# LSM6DSOTR.net
KiCad netlist of a schematic drawn in Altium Designer
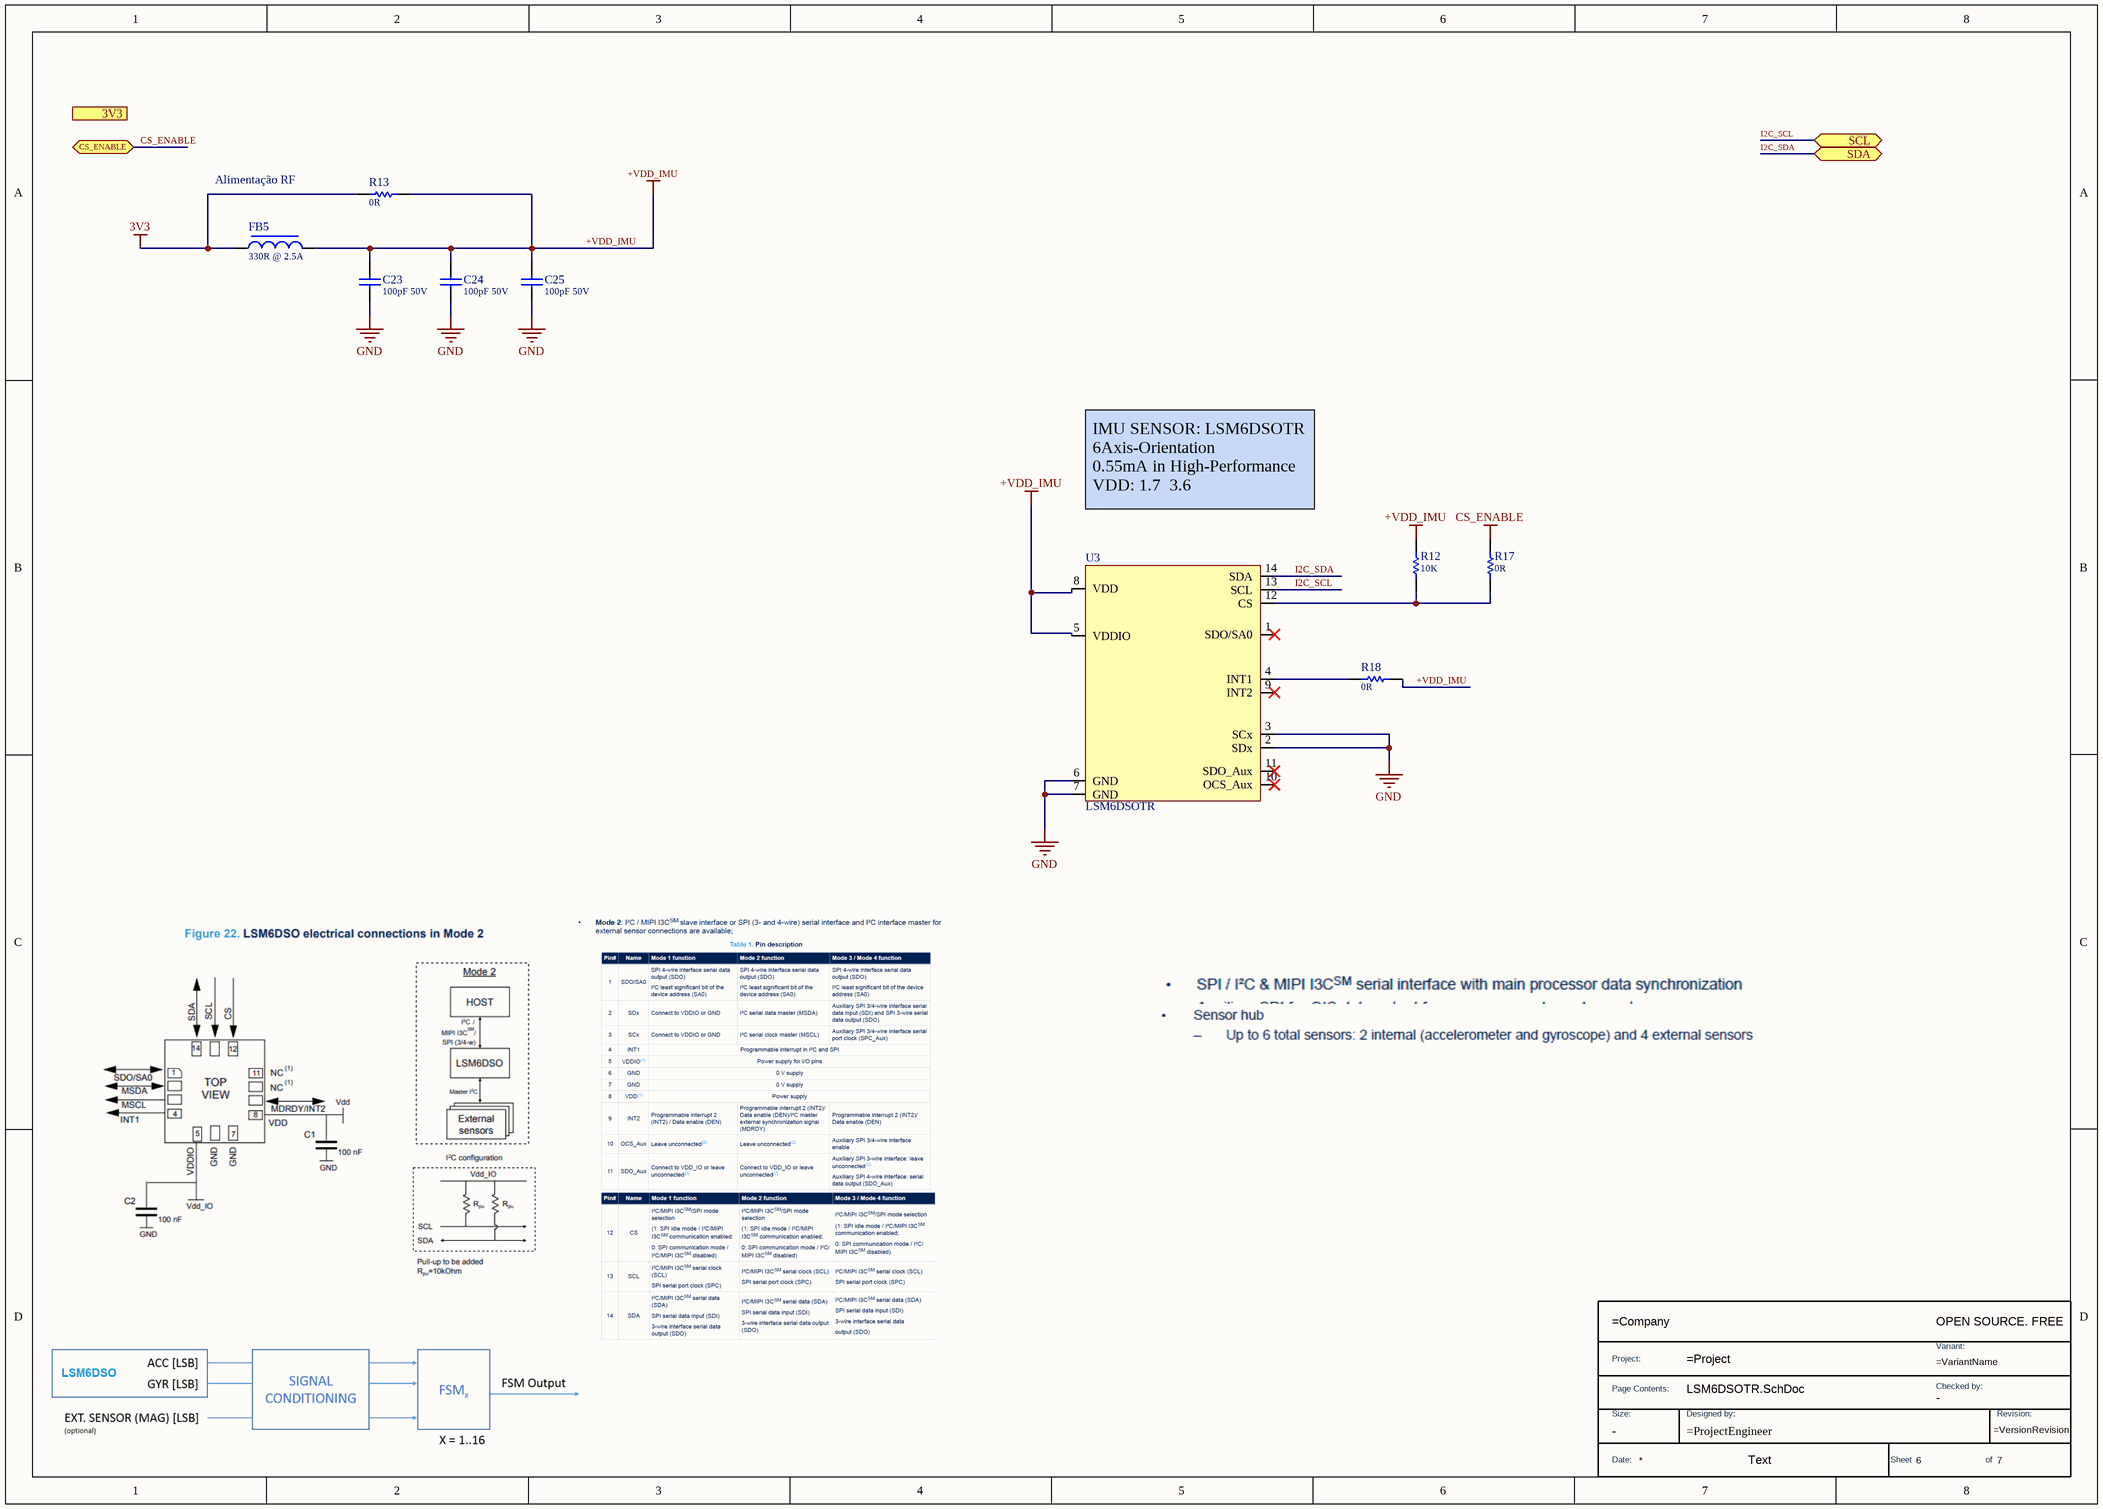
[diagram p0: LSM6DSOTR.SchDoc]

(export (version "E")
  (design (tool "Eeschema 10.0.6"))
  (components
    (comp (ref "C23")
      (value "CC0805JRNPO9BN101")
      (footprint "CAP_0805")
      (description "CAP CER 100PF 50V C0G/NPO 0805")
      (fields (field (name "MANUFACTURER") "YAGEO") (field (name "VALOR") "100pF 50V"))
      (libsource (lib "OBDH_Ed02") (part "CC0805JRNPO9BN101"))
    )
    (comp (ref "C24")
      (value "CC0805JRNPO9BN101")
      (footprint "CAP_0805")
      (description "CAP CER 100PF 50V C0G/NPO 0805")
      (fields (field (name "MANUFACTURER") "YAGEO") (field (name "VALOR") "100pF 50V"))
      (libsource (lib "OBDH_Ed02") (part "CC0805JRNPO9BN101"))
    )
    (comp (ref "C25")
      (value "CC0805JRNPO9BN101")
      (footprint "CAP_0805")
      (description "CAP CER 100PF 50V C0G/NPO 0805")
      (fields (field (name "MANUFACTURER") "YAGEO") (field (name "VALOR") "100pF 50V"))
      (libsource (lib "OBDH_Ed02") (part "CC0805JRNPO9BN101"))
    )
    (comp (ref "FB5")
      (value "MPZ2012S331AT000")
      (footprint "IND_0805")
      (description "FERRITE BEAD 330 OHM 0805 1LN")
      (fields (field (name "MANUFACTURER") "TDK Corporation") (field (name "VALOR") "330R @ 2.5A"))
      (libsource (lib "OBDH_Ed02") (part "MPZ2012S331AT000"))
    )
    (comp (ref "R12")
      (value "AF0805JR-0710KL")
      (footprint "RES_0805")
      (description "RES SMD 10K OHM 5% 1/8W 0805")
      (fields (field (name "MANUFACTURER") "YAGEO") (field (name "VALOR") "10K"))
      (libsource (lib "OBDH_Ed02") (part "AF0805JR-0710KL"))
    )
    (comp (ref "R13")
      (value "RC0805JR-070RL")
      (footprint "RES_0805")
      (description "RES 0 OHM JUMPER 1/8W 0805")
      (fields (field (name "MANUFACTURER") "YAGEO") (field (name "VALOR") "0R"))
      (libsource (lib "OBDH_Ed02") (part "RC0805JR-070RL"))
    )
    (comp (ref "R17")
      (value "RC0805JR-070RL")
      (footprint "RES_0805")
      (description "RES 0 OHM JUMPER 1/8W 0805")
      (fields (field (name "MANUFACTURER") "YAGEO") (field (name "VALOR") "0R"))
      (libsource (lib "OBDH_Ed02") (part "RC0805JR-070RL"))
    )
    (comp (ref "R18")
      (value "RC0805JR-070RL")
      (footprint "RES_0805")
      (description "RES 0 OHM JUMPER 1/8W 0805")
      (fields (field (name "MANUFACTURER") "YAGEO") (field (name "VALOR") "0R"))
      (libsource (lib "OBDH_Ed02") (part "RC0805JR-070RL"))
    )
    (comp (ref "U3")
      (value "LSM6DSOTR")
      (footprint "IC_IIM-42351")
      (description "Accelerometer, Gyroscope, 6 Axis Sensor I²C, SPI Output")
      (libsource (lib "OBDH_Ed02") (part "LSM6DSOTR"))
    )
  )
  (nets
    (net (code "1") (name "+VDD_IMU") (class "Default")
      (node (ref "C23") (pin "2") (pinfunction "2_2") (pintype "passive"))
      (node (ref "C24") (pin "2") (pinfunction "2_2") (pintype "passive"))
      (node (ref "C25") (pin "2") (pinfunction "2_2") (pintype "passive"))
      (node (ref "FB5") (pin "2") (pinfunction "2_2") (pintype "passive"))
      (node (ref "R12") (pin "2") (pinfunction "2_2") (pintype "passive"))
      (node (ref "R13") (pin "2") (pinfunction "2_2") (pintype "passive"))
      (node (ref "R18") (pin "2") (pinfunction "2_2") (pintype "passive"))
      (node (ref "U3") (pin "5") (pinfunction "VDDIO_5") (pintype "power_in"))
      (node (ref "U3") (pin "8") (pinfunction "VDD_8") (pintype "power_in"))
    )
    (net (code "2") (name "/I2C_SCL") (class "Default")
      (node (ref "U3") (pin "13") (pinfunction "SCL_13") (pintype "bidirectional"))
    )
    (net (code "3") (name "/I2C_SDA") (class "Default")
      (node (ref "U3") (pin "14") (pinfunction "SDA_14") (pintype "bidirectional"))
    )
    (net (code "4") (name "3V3") (class "Default")
      (node (ref "FB5") (pin "1") (pinfunction "1_1") (pintype "passive"))
      (node (ref "R13") (pin "1") (pinfunction "1_1") (pintype "passive"))
    )
    (net (code "5") (name "CS_ENABLE") (class "Default")
      (node (ref "R17") (pin "2") (pinfunction "2_2") (pintype "passive"))
    )
    (net (code "6") (name "GND") (class "Default")
      (node (ref "C23") (pin "1") (pinfunction "1_1") (pintype "passive"))
      (node (ref "C24") (pin "1") (pinfunction "1_1") (pintype "passive"))
      (node (ref "C25") (pin "1") (pinfunction "1_1") (pintype "passive"))
      (node (ref "U3") (pin "2") (pinfunction "SDx_2") (pintype "power_in"))
      (node (ref "U3") (pin "3") (pinfunction "SCx_3") (pintype "power_in"))
      (node (ref "U3") (pin "6") (pinfunction "GND_6") (pintype "power_in"))
      (node (ref "U3") (pin "7") (pinfunction "GND_7") (pintype "power_in"))
    )
    (net (code "7") (name "Net-(U3-CS)") (class "Default")
      (node (ref "R12") (pin "1") (pinfunction "1_1") (pintype "passive"))
      (node (ref "R17") (pin "1") (pinfunction "1_1") (pintype "passive"))
      (node (ref "U3") (pin "12") (pinfunction "CS_12") (pintype "bidirectional"))
    )
    (net (code "8") (name "Net-(U3-INT1)") (class "Default")
      (node (ref "R18") (pin "1") (pinfunction "1_1") (pintype "passive"))
      (node (ref "U3") (pin "4") (pinfunction "INT1_4") (pintype "power_in"))
    )
    (net (code "9") (name "unconnected-(U3-INT2-Pad9)") (class "Default")
      (node (ref "U3") (pin "9") (pinfunction "INT2_9") (pintype "bidirectional+no_connect"))
    )
    (net (code "10") (name "unconnected-(U3-OCS_Aux-Pad10)") (class "Default")
      (node (ref "U3") (pin "10") (pinfunction "OCS_Aux_10") (pintype "bidirectional+no_connect"))
    )
    (net (code "11") (name "unconnected-(U3-SDO_Aux-Pad11)") (class "Default")
      (node (ref "U3") (pin "11") (pinfunction "SDO_Aux_11") (pintype "bidirectional+no_connect"))
    )
    (net (code "12") (name "unconnected-(U3-SDO{slash}SA0-Pad1)") (class "Default")
      (node (ref "U3") (pin "1") (pinfunction "SDO/SA0_1") (pintype "bidirectional+no_connect"))
    )
  )
)
